# UARC_Sensor.net
KiCad netlist of a schematic drawn in Altium Designer
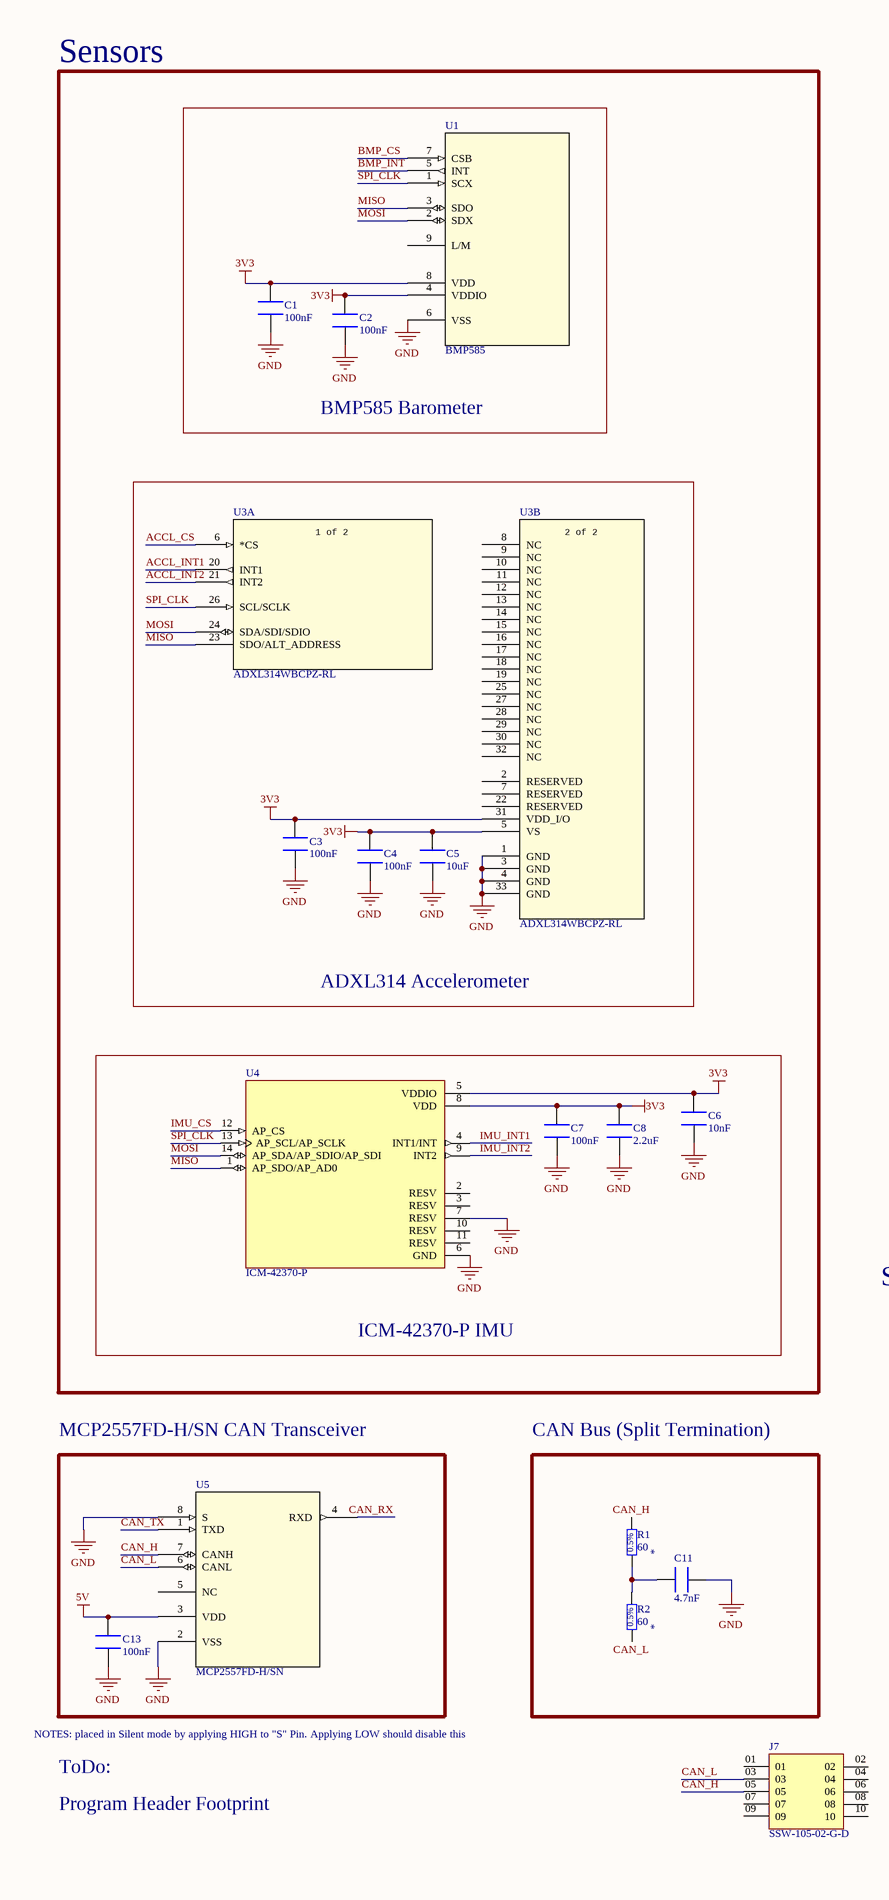
[diagram p0: UARC_Sensor.SchDoc, left]
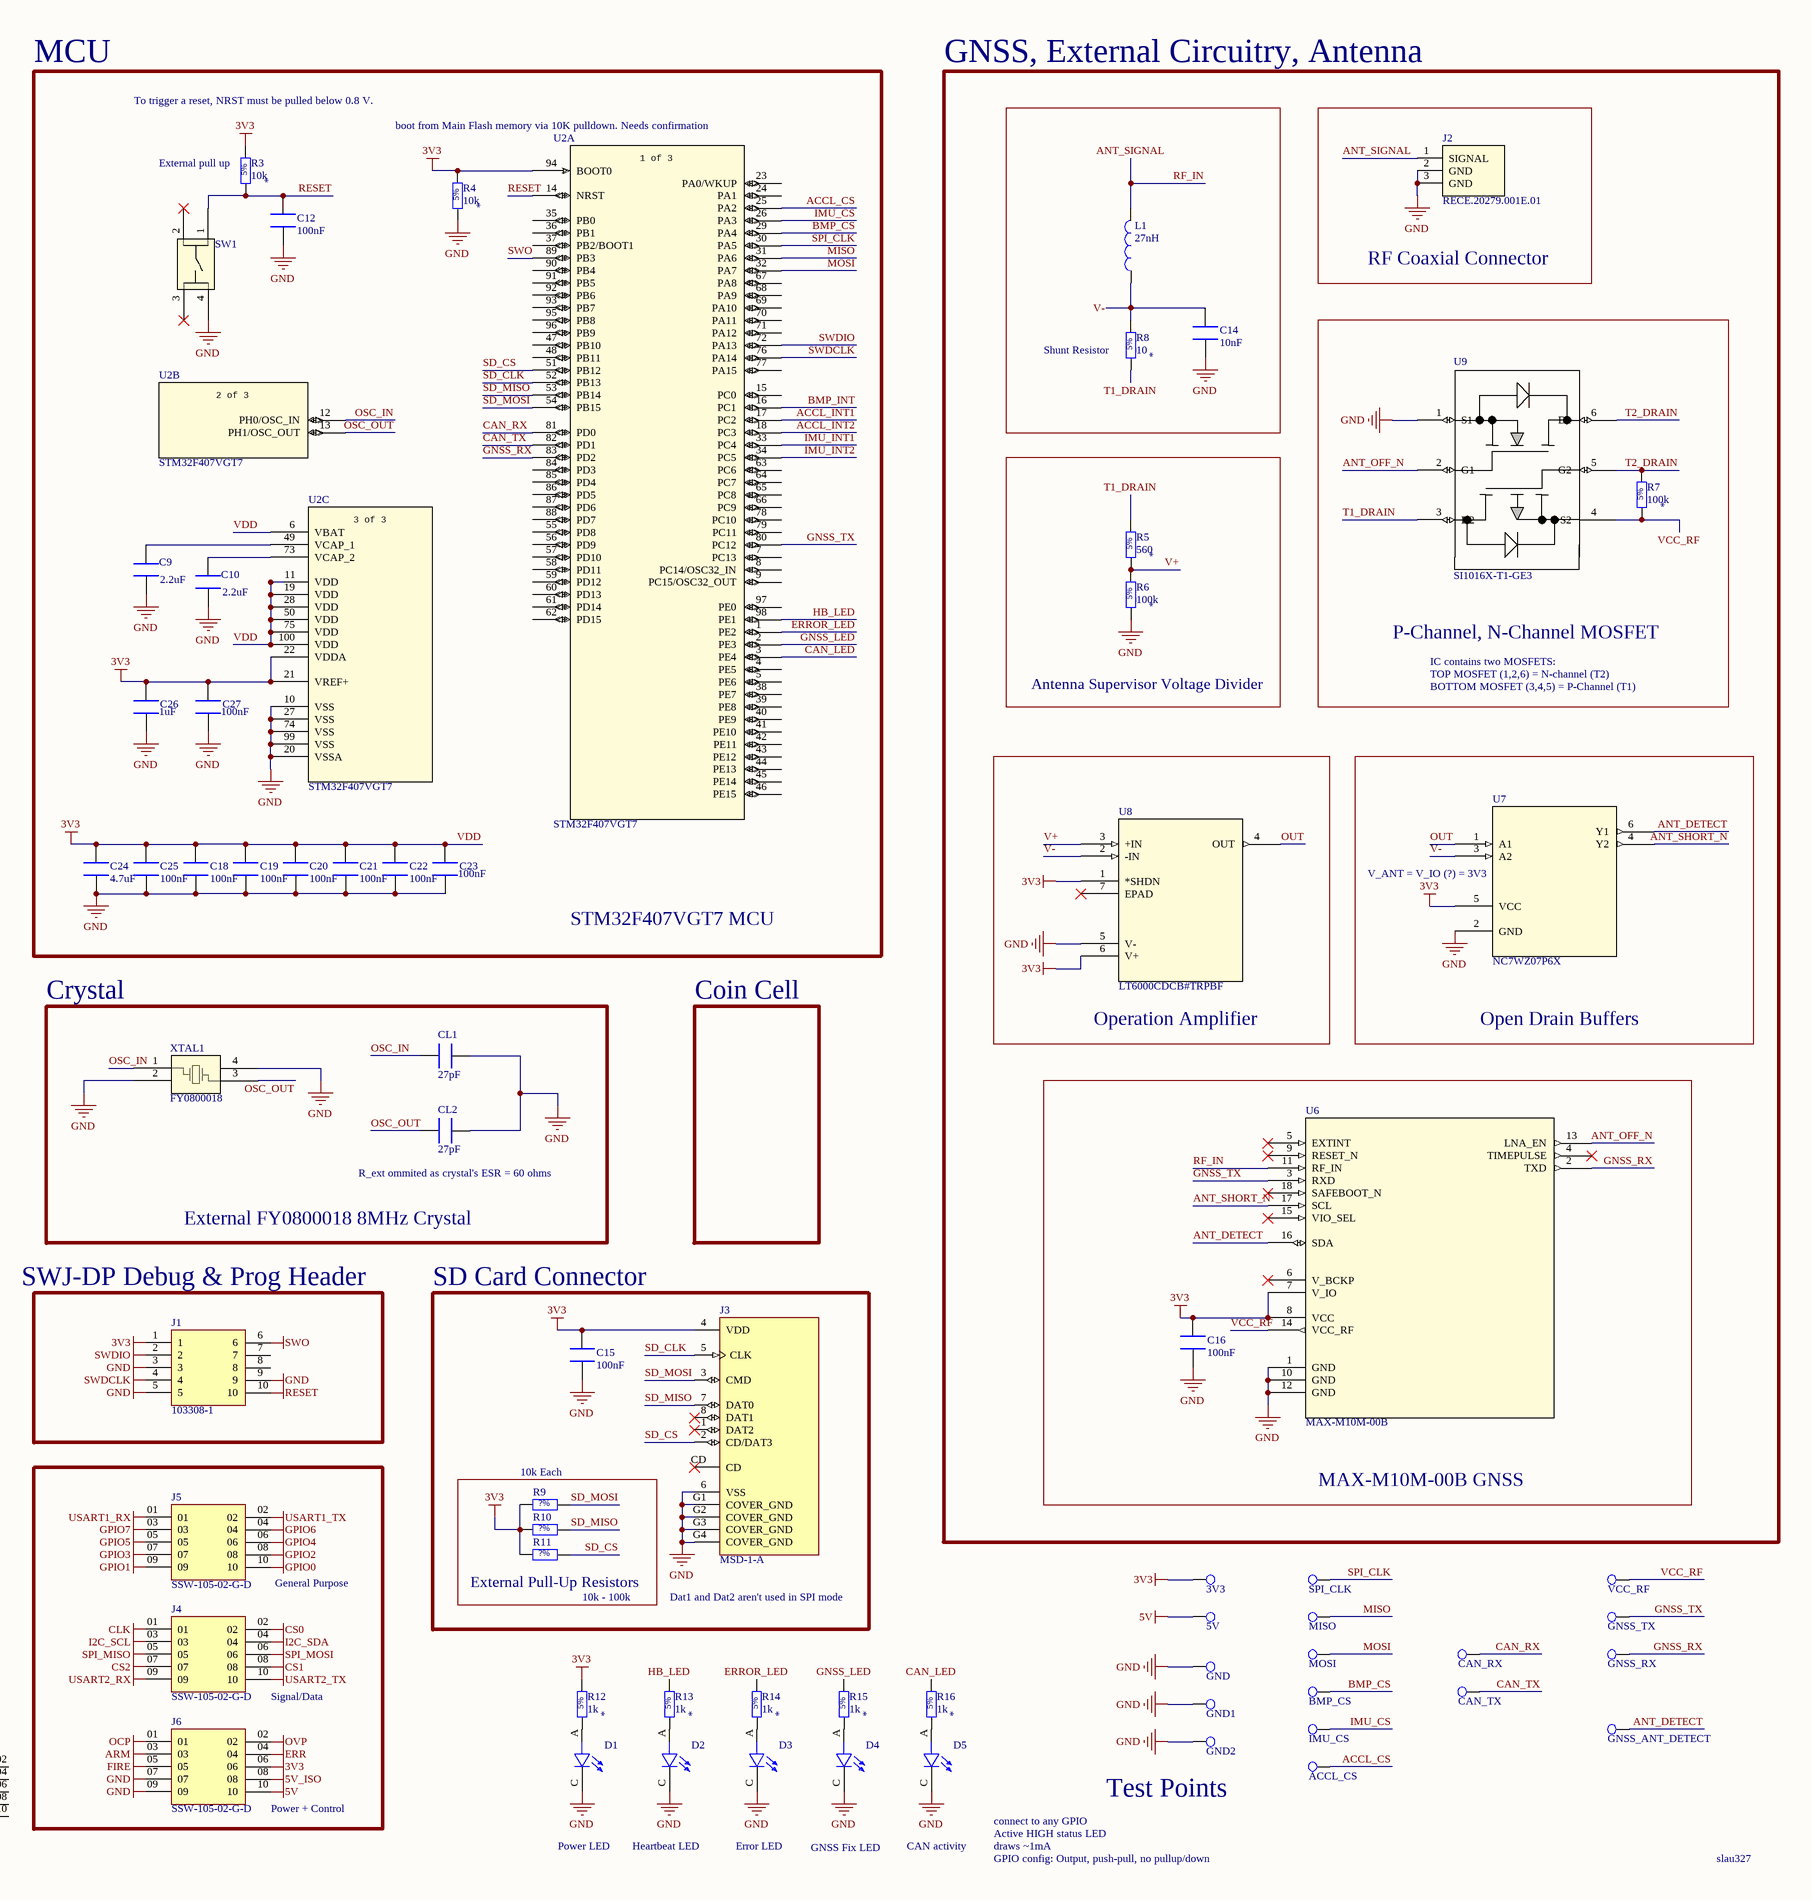
[diagram p1: UARC_Sensor.SchDoc, right]

(export (version "E")
  (design (tool "Eeschema 10.0.6"))
  (components
    (comp (ref "3V3")
      (value "Test Point")
      (footprint "APSS Generic Components:Test Point Pad Large")
      (libsource (lib "APSS Generic Components") (part "Test Point"))
    )
    (comp (ref "5V")
      (value "Test Point")
      (footprint "APSS Generic Components:Test Point Pad Large")
      (libsource (lib "APSS Generic Components") (part "Test Point"))
    )
    (comp (ref "ACCL_CS")
      (value "Test Point")
      (footprint "APSS Generic Components:Test Point Pad Large")
      (libsource (lib "APSS Generic Components") (part "Test Point"))
    )
    (comp (ref "BMP_CS")
      (value "Test Point")
      (footprint "APSS Generic Components:Test Point Pad Large")
      (libsource (lib "APSS Generic Components") (part "Test Point"))
    )
    (comp (ref "C1")
      (value "100nF")
      (footprint "APSS Flight Parts:CAPACITOR_0805_2012M-70N")
      (description "CUSTOM: 885012207016 0.1µF 0805 ±10% 10V X7R Ceramic Capacitor")
      (fields (field (name "TOLERANCE") "±20%") (field (name "MF PART NO.") "GRM21BR61E226ME44L"))
      (libsource (lib "") (part "GRM21BR61E226ME44L_1"))
    )
    (comp (ref "C2")
      (value "100nF")
      (footprint "APSS Flight Parts:CAPACITOR_0805_2012M-70N")
      (description "CUSTOM: 885012207016 0.1µF 0805 ±10% 10V X7R Ceramic Capacitor")
      (fields (field (name "TOLERANCE") "±20%") (field (name "MF PART NO.") "GRM21BR61E226ME44L"))
      (libsource (lib "APSS Flight Parts") (part "GRM21BR61E226ME44L"))
    )
    (comp (ref "C3")
      (value "100nF")
      (footprint "APSS Flight Parts:CAPACITOR_0805_2012M-70N")
      (description "CUSTOM: 885012207016 0.1µF 0805 ±10% 10V X7R Ceramic Capacitor")
      (fields (field (name "TOLERANCE") "±20%") (field (name "MF PART NO.") "GRM21BR61E226ME44L"))
      (libsource (lib "APSS Flight Parts") (part "GRM21BR61E226ME44L"))
    )
    (comp (ref "C4")
      (value "100nF")
      (footprint "APSS Flight Parts:CAPACITOR_0805_2012M-70N")
      (description "CUSTOM: 885012207016 0.1µF 0805 ±10% 10V X7R Ceramic Capacitor")
      (fields (field (name "TOLERANCE") "±20%") (field (name "MF PART NO.") "GRM21BR61E226ME44L"))
      (libsource (lib "APSS Flight Parts") (part "GRM21BR61E226ME44L"))
    )
    (comp (ref "C5")
      (value "10uF")
      (footprint "APSS Flight Parts:CAPACITOR_0805_2012M-70N")
      (description "CUSTOM: TACR106K010XTA 10µF 0805 ±10% 10V Tantalum Capacitor")
      (fields (field (name "TOLERANCE") "±20%") (field (name "MF PART NO.") "GRM21BR61E226ME44L"))
      (libsource (lib "APSS Flight Parts") (part "GRM21BR61E226ME44L"))
    )
    (comp (ref "C6")
      (value "10nF")
      (footprint "APSS Flight Parts:CAPACITOR_0805_2012M-70N")
      (description "CUSTOM: 885012207011, 10000pF 0805 ±10% 10 X7R  Ceramic Capacitor")
      (fields (field (name "TOLERANCE") "±20%") (field (name "MF PART NO.") "GRM21BR61E226ME44L"))
      (libsource (lib "APSS Flight Parts") (part "GRM21BR61E226ME44L"))
    )
    (comp (ref "C7")
      (value "100nF")
      (footprint "APSS Flight Parts:CAPACITOR_0805_2012M-70N")
      (description "CUSTOM: 885012207016 0.1µF 0805 ±10% 10V X7R Ceramic Capacitor")
      (fields (field (name "TOLERANCE") "±20%") (field (name "MF PART NO.") "GRM21BR61E226ME44L"))
      (libsource (lib "APSS Flight Parts") (part "GRM21BR61E226ME44L"))
    )
    (comp (ref "C8")
      (value "2.2uF")
      (footprint "APSS Flight Parts:CAPACITOR_0805_2012M-70N")
      (description "CUSTOM: GRM21BR71A225KA01L 2.2µF 0805 ±10% 10V X7R Ceramic Capacitor")
      (fields (field (name "TOLERANCE") "±20%") (field (name "MF PART NO.") "GRM21BR61E226ME44L"))
      (libsource (lib "APSS Flight Parts") (part "GRM21BR61E226ME44L"))
    )
    (comp (ref "C9")
      (value "2.2uF")
      (footprint "APSS Flight Parts:CAPACITOR_0805_2012M-70N")
      (description "CUSTOM: GRM21BR71A225KA01L 2.2µF 0805 ±10% 10V X7R Ceramic Capacitor")
      (fields (field (name "TOLERANCE") "±20%") (field (name "MF PART NO.") "GRM21BR61E226ME44L"))
      (libsource (lib "APSS Flight Parts") (part "GRM21BR61E226ME44L"))
    )
    (comp (ref "C10")
      (value "2.2uF")
      (footprint "APSS Flight Parts:CAPACITOR_0805_2012M-70N")
      (description "CUSTOM: GRM21BR71A225KA01L 2.2µF 0805 ±10% 10V X7R Ceramic Capacitor")
      (fields (field (name "TOLERANCE") "±20%") (field (name "MF PART NO.") "GRM21BR61E226ME44L"))
      (libsource (lib "APSS Flight Parts") (part "GRM21BR61E226ME44L"))
    )
    (comp (ref "C11")
      (value "4.7nF")
      (footprint "APSS Flight Parts:CAPACITOR_0805_2012M-70N")
      (description "CUSTOM: CC0805KRX7R9BB472 4700pF 0805 ±10% 50V X7R Ceramic Capacitor")
      (fields (field (name "TOLERANCE") "±20%") (field (name "MF PART NO.") "GRM21BR61E226ME44L"))
      (libsource (lib "APSS Flight Parts") (part "GRM21BR61E226ME44L"))
    )
    (comp (ref "C12")
      (value "100nF")
      (footprint "APSS Flight Parts:CAPACITOR_0805_2012M-70N")
      (description "CUSTOM: 885012207016 0.1µF 0805 ±10% 10V X7R Ceramic Capacitor")
      (fields (field (name "TOLERANCE") "±20%") (field (name "MF PART NO.") "GRM21BR61E226ME44L"))
      (libsource (lib "APSS Flight Parts") (part "GRM21BR61E226ME44L"))
    )
    (comp (ref "C13")
      (value "100nF")
      (footprint "APSS Flight Parts:CAPACITOR_0805_2012M-70N")
      (description "CUSTOM: 885012207016 0.1µF 0805 ±10% 10V X7R Ceramic Capacitor")
      (fields (field (name "TOLERANCE") "±20%") (field (name "MF PART NO.") "GRM21BR60J107ME15L"))
      (libsource (lib "APSS Flight Parts") (part "GRM21BR60J107ME15L"))
    )
    (comp (ref "C14")
      (value "10nF")
      (footprint "APSS Flight Parts:CAPACITOR_0402_1005M_55N")
      (description "CUSTOM: GRM155R71C103KA01D, 10000pF 0402 ±10% 16V X7R Ceramic Capacitor")
      (fields (field (name "TOLERANCE") "±10%") (field (name "MF PART NO.") "GRM155R61E225KE11J"))
      (libsource (lib "APSS Flight Parts") (part "GRM155R61E225KE11J"))
    )
    (comp (ref "C15")
      (value "100nF")
      (footprint "APSS Flight Parts:CAPACITOR_0805_2012M-70N")
      (description "CUSTOM: 885012207016 0.1µF 0805 ±10% 10V X7R Ceramic Capacitor")
      (fields (field (name "TOLERANCE") "±20%") (field (name "MF PART NO.") "GRM21BR61E226ME44L"))
      (libsource (lib "") (part "GRM21BR61E226ME44L_1"))
    )
    (comp (ref "C16")
      (value "100nF")
      (footprint "APSS Flight Parts:CAPACITOR_0805_2012M-70N")
      (description "CUSTOM: 885012207016 0.1µF 0805 ±10% 10V X7R Ceramic Capacitor")
      (fields (field (name "TOLERANCE") "±20%") (field (name "MF PART NO.") "GRM21BR61E226ME44L"))
      (libsource (lib "") (part "GRM21BR61E226ME44L_1"))
    )
    (comp (ref "C18")
      (value "100nF")
      (footprint "APSS Flight Parts:CAPACITOR_0805_2012M-70N")
      (description "CUSTOM: 885012207016 0.1µF 0805 ±10% 10V X7R Ceramic Capacitor")
      (fields (field (name "TOLERANCE") "±20%") (field (name "MF PART NO.") "GRM21BR61E226ME44L"))
      (libsource (lib "APSS Flight Parts") (part "GRM21BR61E226ME44L"))
    )
    (comp (ref "C19")
      (value "100nF")
      (footprint "APSS Flight Parts:CAPACITOR_0805_2012M-70N")
      (description "CUSTOM: 885012207016 0.1µF 0805 ±10% 10V X7R Ceramic Capacitor")
      (fields (field (name "TOLERANCE") "±20%") (field (name "MF PART NO.") "GRM21BR61E226ME44L"))
      (libsource (lib "APSS Flight Parts") (part "GRM21BR61E226ME44L"))
    )
    (comp (ref "C20")
      (value "100nF")
      (footprint "APSS Flight Parts:CAPACITOR_0805_2012M-70N")
      (description "CUSTOM: 885012207016 0.1µF 0805 ±10% 10V X7R Ceramic Capacitor")
      (fields (field (name "TOLERANCE") "±20%") (field (name "MF PART NO.") "GRM21BR61E226ME44L"))
      (libsource (lib "APSS Flight Parts") (part "GRM21BR61E226ME44L"))
    )
    (comp (ref "C21")
      (value "100nF")
      (footprint "APSS Flight Parts:CAPACITOR_0805_2012M-70N")
      (description "CUSTOM: 885012207016 0.1µF 0805 ±10% 10V X7R Ceramic Capacitor")
      (fields (field (name "TOLERANCE") "±20%") (field (name "MF PART NO.") "GRM21BR61E226ME44L"))
      (libsource (lib "APSS Flight Parts") (part "GRM21BR61E226ME44L"))
    )
    (comp (ref "C22")
      (value "100nF")
      (footprint "APSS Flight Parts:CAPACITOR_0805_2012M-70N")
      (description "CUSTOM: 885012207016 0.1µF 0805 ±10% 10V X7R Ceramic Capacitor")
      (fields (field (name "TOLERANCE") "±20%") (field (name "MF PART NO.") "GRM21BR61E226ME44L"))
      (libsource (lib "APSS Flight Parts") (part "GRM21BR61E226ME44L"))
    )
    (comp (ref "C23")
      (value "100nF")
      (footprint "APSS Flight Parts:CAPACITOR_0805_2012M-70N")
      (description "CUSTOM: 885012207016 0.1µF 0805 ±10% 10V X7R Ceramic Capacitor")
      (fields (field (name "TOLERANCE") "±20%") (field (name "MF PART NO.") "GRM21BR61E226ME44L"))
      (libsource (lib "APSS Flight Parts") (part "GRM21BR61E226ME44L"))
    )
    (comp (ref "C24")
      (value "4.7uF")
      (footprint "APSS Flight Parts:CAPACITOR_0603_1608M_100N")
      (description "CUSTOM:  GRM188Z71A475KE15D 4.7µF 0603 ±10% 10V X7R Ceramic Capacitor")
      (fields (field (name "TOLERANCE") "±10%") (field (name "MF PART NO.") "GRM188Z71A106KA73D"))
      (libsource (lib "APSS Flight Parts") (part "GRM188Z71A106KA73D"))
    )
    (comp (ref "C25")
      (value "100nF")
      (footprint "APSS Flight Parts:CAPACITOR_0805_2012M-70N")
      (description "CUSTOM: 885012207016 0.1µF 0805 ±10% 10V X7R Ceramic Capacitor")
      (fields (field (name "TOLERANCE") "±20%") (field (name "MF PART NO.") "GRM21BR61E226ME44L"))
      (libsource (lib "APSS Flight Parts") (part "GRM21BR61E226ME44L"))
    )
    (comp (ref "C26")
      (value "1uF")
      (footprint "APSS Flight Parts:CAPACITOR_0805_2012M-70N")
      (description "CUSTOM: 0805ZC105KAT2A 1µF 0805 ±10% 10V X7R  Ceramic Capacitor")
      (fields (field (name "TOLERANCE") "±20%") (field (name "MF PART NO.") "GRM21BR61E226ME44L"))
      (libsource (lib "APSS Flight Parts") (part "GRM21BR61E226ME44L"))
    )
    (comp (ref "C27")
      (value "100nF")
      (footprint "APSS Flight Parts:CAPACITOR_0805_2012M-70N")
      (description "CUSTOM: 885012207016 0.1µF 0805 ±10% 10V X7R Ceramic Capacitor")
      (fields (field (name "TOLERANCE") "±20%") (field (name "MF PART NO.") "GRM21BR61E226ME44L"))
      (libsource (lib "APSS Flight Parts") (part "GRM21BR61E226ME44L"))
    )
    (comp (ref "CAN_RX")
      (value "Test Point")
      (footprint "APSS Generic Components:Test Point Pad Large")
      (libsource (lib "APSS Generic Components") (part "Test Point"))
    )
    (comp (ref "CAN_TX")
      (value "Test Point")
      (footprint "APSS Generic Components:Test Point Pad Large")
      (libsource (lib "APSS Generic Components") (part "Test Point"))
    )
    (comp (ref "CL1")
      (value "27pF")
      (footprint "APSS Flight Parts:CAPACITOR_0805_2012M-70N")
      (description "CUSTOM: 600F270JT250XT4K 27pF 0805 ±5% 250V C0G, NP0 Ceramic Capacitor")
      (fields (field (name "TOLERANCE") "±20%") (field (name "MF PART NO.") "GRM21BR61E226ME44L"))
      (libsource (lib "APSS Flight Parts") (part "GRM21BR61E226ME44L"))
    )
    (comp (ref "CL2")
      (value "27pF")
      (footprint "APSS Flight Parts:CAPACITOR_0805_2012M-70N")
      (description "CUSTOM: 600F270JT250XT4K 27pF 0805 ±5% 250V C0G, NP0 Ceramic Capacitor")
      (fields (field (name "TOLERANCE") "±20%") (field (name "MF PART NO.") "GRM21BR61E226ME44L"))
      (libsource (lib "APSS Flight Parts") (part "GRM21BR61E226ME44L"))
    )
    (comp (ref "D1")
      (value "SML-D12U1WT86")
      (footprint "Custom_Footprints:LED_SML-D12U1WT86")
      (description "Red 620nm LED Indication - Discrete 2.2V 0603 (1608 Metric)")
      (fields (field (name "MF") "Rohm"))
      (libsource (lib "Custom_Library") (part "SML-D12U1WT86"))
    )
    (comp (ref "D2")
      (value "SML-D12U1WT86")
      (footprint "Custom_Footprints:LED_SML-D12U1WT86")
      (description "Red 620nm LED Indication - Discrete 2.2V 0603 (1608 Metric)")
      (fields (field (name "MF") "Rohm"))
      (libsource (lib "Custom_Library") (part "SML-D12U1WT86"))
    )
    (comp (ref "D3")
      (value "SML-D12U1WT86")
      (footprint "Custom_Footprints:LED_SML-D12U1WT86")
      (description "Red 620nm LED Indication - Discrete 2.2V 0603 (1608 Metric)")
      (fields (field (name "MF") "Rohm"))
      (libsource (lib "Custom_Library") (part "SML-D12U1WT86"))
    )
    (comp (ref "D4")
      (value "SML-D12U1WT86")
      (footprint "Custom_Footprints:LED_SML-D12U1WT86")
      (description "Red 620nm LED Indication - Discrete 2.2V 0603 (1608 Metric)")
      (fields (field (name "MF") "Rohm"))
      (libsource (lib "Custom_Library") (part "SML-D12U1WT86"))
    )
    (comp (ref "D5")
      (value "SML-D12U1WT86")
      (footprint "Custom_Footprints:LED_SML-D12U1WT86")
      (description "Red 620nm LED Indication - Discrete 2.2V 0603 (1608 Metric)")
      (fields (field (name "MF") "Rohm"))
      (libsource (lib "Custom_Library") (part "SML-D12U1WT86"))
    )
    (comp (ref "GND")
      (value "Test Point")
      (footprint "APSS Generic Components:Test Point Pad Large")
      (libsource (lib "APSS Generic Components") (part "Test Point"))
    )
    (comp (ref "GND1")
      (value "Test Point")
      (footprint "APSS Generic Components:Test Point Pad Large")
      (libsource (lib "APSS Generic Components") (part "Test Point"))
    )
    (comp (ref "GND2")
      (value "Test Point")
      (footprint "APSS Generic Components:Test Point Pad Large")
      (libsource (lib "APSS Generic Components") (part "Test Point"))
    )
    (comp (ref "GNSS_ANT_DETECT")
      (value "Test Point")
      (footprint "APSS Generic Components:Test Point Pad Large")
      (libsource (lib "APSS Generic Components") (part "Test Point"))
    )
    (comp (ref "GNSS_RX")
      (value "Test Point")
      (footprint "APSS Generic Components:Test Point Pad Large")
      (libsource (lib "APSS Generic Components") (part "Test Point"))
    )
    (comp (ref "GNSS_TX")
      (value "Test Point")
      (footprint "APSS Generic Components:Test Point Pad Large")
      (libsource (lib "APSS Generic Components") (part "Test Point"))
    )
    (comp (ref "IMU_CS")
      (value "Test Point")
      (footprint "APSS Generic Components:Test Point Pad Large")
      (libsource (lib "APSS Generic Components") (part "Test Point"))
    )
    (comp (ref "J1")
      (value "103308-1")
      (footprint "Custom_Footprints:TE_103308-1")
      (description "Header;  Pin;  Vertical;  Copper Alloy;  Thermoplastic;  10;  0.100 x 0.100 in.;  1 A")
      (fields (field (name "MF") "TE Connectivity"))
      (libsource (lib "Custom_Library") (part "103308-1"))
    )
    (comp (ref "J2")
      (value "RECE.20279.001E.01")
      (footprint "Custom_Footprints:CON3_RECE.20279.001E.01_TAL")
      (description "No Description Available")
      (fields (field (name "COPYRIGHT") "Copyright (C) 2025 Ultra Librarian. All rights reserved."))
      (libsource (lib "Custom_Library") (part "RECE.20279.001E.01"))
    )
    (comp (ref "J3")
      (value "MSD-1-A")
      (footprint "Custom_Footprints:CUI_MSD-1-A")
      (fields (field (name "MF") "Same Sky"))
      (libsource (lib "Custom_Library") (part "MSD-1-A"))
    )
    (comp (ref "J4")
      (value "SSW-105-02-G-D")
      (footprint "Custom_Footprints:SAMTEC_SSW-105-02-G-D")
      (fields (field (name "MF") "Samtec Inc."))
      (libsource (lib "Custom_Library") (part "SSW-105-02-G-D"))
    )
    (comp (ref "J5")
      (value "SSW-105-02-G-D")
      (footprint "Custom_Footprints:SAMTEC_SSW-105-02-G-D")
      (fields (field (name "MF") "Samtec Inc."))
      (libsource (lib "Custom_Library") (part "SSW-105-02-G-D"))
    )
    (comp (ref "J6")
      (value "SSW-105-02-G-D")
      (footprint "Custom_Footprints:SAMTEC_SSW-105-02-G-D")
      (fields (field (name "MF") "Samtec Inc."))
      (libsource (lib "Custom_Library") (part "SSW-105-02-G-D"))
    )
    (comp (ref "J7")
      (value "SSW-105-02-G-D")
      (footprint "Custom_Footprints:SAMTEC_SSW-105-02-G-D")
      (fields (field (name "MF") "Samtec Inc."))
      (libsource (lib "Custom_Library") (part "SSW-105-02-G-D"))
    )
    (comp (ref "L1")
      (value "27nH")
      (footprint "Custom_Footprints:INDC1005X55N")
      (description "LQG15HN2N2S02D 27nH 0402  Unshielded Multilayer Inductor 350 mA 460mOhm Max")
      (fields (field (name "MP") "LQG15HH27NJ02D"))
      (libsource (lib "Custom_Library") (part "LQG15HH27NJ02D"))
    )
    (comp (ref "MISO")
      (value "Test Point")
      (footprint "APSS Generic Components:Test Point Pad Large")
      (libsource (lib "APSS Generic Components") (part "Test Point"))
    )
    (comp (ref "MOSI")
      (value "Test Point")
      (footprint "APSS Generic Components:Test Point Pad Large")
      (libsource (lib "APSS Generic Components") (part "Test Point"))
    )
    (comp (ref "R1")
      (value "60")
      (footprint "APSS Flight Parts:RESISTOR_1206_3216M_55N")
      (description "CUSTOM: CRCW120660R0KNEAIF 60 Ohms 1206  ±10% 0.25W, 1/4W Chip Resistor,")
      (fields
        (field (name "TOLERANCE") "0.5%")
        (field (name "POWER") "0.52W")
        (field (name "MF PART NO.") "*")
      )
      (libsource (lib "APSS Flight Parts") (part "TNPW1206xxxxDE Series"))
    )
    (comp (ref "R2")
      (value "60")
      (footprint "APSS Flight Parts:RESISTOR_1206_3216M_55N")
      (description "CUSTOM: CRCW120660R0KNEAIF 60 Ohms 1206  ±10% 0.25W, 1/4W Chip Resistor,")
      (fields
        (field (name "TOLERANCE") "0.5%")
        (field (name "POWER") "0.52W")
        (field (name "MF PART NO.") "*")
      )
      (libsource (lib "APSS Flight Parts") (part "TNPW1206xxxxDE Series"))
    )
    (comp (ref "R3")
      (value "10k")
      (footprint "APSS Flight Parts:Resistor_0805_2012M-50N")
      (description "CUSTOM: CRCW080510K0FKEA 10 kOhms 0805  ±1% 0.25W, 1/4W Chip Resistor")
      (fields (field (name "TOLERANCE") "5%") (field (name "POWER") "1/8W") (field (name "MF PART NO.") "*"))
      (libsource (lib "APSS Flight Parts") (part "RMCF0805JT Series"))
    )
    (comp (ref "R4")
      (value "10k")
      (footprint "APSS Flight Parts:Resistor_0805_2012M-50N")
      (description "CUSTOM: CRCW080510K0FKEA 10 kOhms 0805  ±1% 0.25W, 1/4W Chip Resistor")
      (fields (field (name "TOLERANCE") "5%") (field (name "POWER") "1/8W") (field (name "MF PART NO.") "*"))
      (libsource (lib "APSS Flight Parts") (part "RMCF0805JT Series"))
    )
    (comp (ref "R5")
      (value "560")
      (footprint "APSS Flight Parts:RESISTOR_0402_1005M_37N")
      (description "CUSTOM: ERJ-2GEJ561X 560 Ohms 0402  ±5% 0.1W, 1/10W Chip Resistor")
      (fields (field (name "TOLERANCE") "5%") (field (name "POWER") "1/16W") (field (name "MF PART NO.") "*"))
      (libsource (lib "APSS Flight Parts") (part "RMCF0402JT Series"))
    )
    (comp (ref "R6")
      (value "100k")
      (footprint "APSS Flight Parts:RESISTOR_0402_1005M_37N")
      (description "CUSTOM: RK73B1ETTP104J 100 kOhms 0402 ±5% 0.1W, 1/10W Chip Resistor")
      (fields (field (name "TOLERANCE") "5%") (field (name "POWER") "1/16W") (field (name "MF PART NO.") "*"))
      (libsource (lib "APSS Flight Parts") (part "RMCF0402JT Series"))
    )
    (comp (ref "R7")
      (value "100k")
      (footprint "APSS Flight Parts:RESISTOR_0402_1005M_37N")
      (description "CUSTOM: RK73B1ETTP104J 100 kOhms 0402 ±5% 0.1W, 1/10W Chip Resistor")
      (fields (field (name "TOLERANCE") "5%") (field (name "POWER") "1/16W") (field (name "MF PART NO.") "*"))
      (libsource (lib "APSS Flight Parts") (part "RMCF0402JT Series"))
    )
    (comp (ref "R8")
      (value "10")
      (footprint "APSS Flight Parts:RESISTOR_0402_1005M_37N")
      (description "CUSTOM: SG73P1EWTTP100J 10 Ohms 0402 ±5% 0.25W, 1/4W Chip Resistor")
      (fields (field (name "TOLERANCE") "5%") (field (name "POWER") "1/16W") (field (name "MF PART NO.") "*"))
      (libsource (lib "APSS Flight Parts") (part "RMCF0402JT Series"))
    )
    (comp (ref "R9")
      (value "~")
      (footprint "RESISTOR_0805_2012M-50N")
      (description "CUSTOM: CRCW080510K0FKEA 10 kOhms 0805  ±1% 0.25W, 1/4W Chip Resistor")
      (fields (field (name "TOLERANCE") "?%"))
      (libsource (lib "APSS Generic Components") (part "Generic Resistor"))
    )
    (comp (ref "R10")
      (value "~")
      (footprint "RESISTOR_0805_2012M-50N")
      (description "CUSTOM: CRCW080510K0FKEA 10 kOhms 0805  ±1% 0.25W, 1/4W Chip Resistor")
      (fields (field (name "TOLERANCE") "?%"))
      (libsource (lib "APSS Generic Components") (part "Generic Resistor"))
    )
    (comp (ref "R11")
      (value "~")
      (footprint "RESISTOR_0805_2012M-50N")
      (description "CUSTOM: CRCW080510K0FKEA 10 kOhms 0805  ±1% 0.25W, 1/4W Chip Resistor")
      (fields (field (name "TOLERANCE") "?%"))
      (libsource (lib "APSS Generic Components") (part "Generic Resistor"))
    )
    (comp (ref "R12")
      (value "1k")
      (footprint "APSS Flight Parts:Resistor_0805_2012M-50N")
      (description "CUSTOM: CRCW08051K00FKEA 1 kOhms 0805 ±1% 0.25W, 1/4W Chip Resistor")
      (fields (field (name "TOLERANCE") "5%") (field (name "POWER") "1/8W") (field (name "MF PART NO.") "*"))
      (libsource (lib "APSS Flight Parts") (part "RMCF0805JT Series"))
    )
    (comp (ref "R13")
      (value "1k")
      (footprint "APSS Flight Parts:Resistor_0805_2012M-50N")
      (description "CUSTOM: CRCW08051K00FKEA 1 kOhms 0805 ±1% 0.25W, 1/4W Chip Resistor")
      (fields (field (name "TOLERANCE") "5%") (field (name "POWER") "1/8W") (field (name "MF PART NO.") "*"))
      (libsource (lib "APSS Flight Parts") (part "RMCF0805JT Series"))
    )
    (comp (ref "R14")
      (value "1k")
      (footprint "APSS Flight Parts:Resistor_0805_2012M-50N")
      (description "CUSTOM: CRCW08051K00FKEA 1 kOhms 0805 ±1% 0.25W, 1/4W Chip Resistor")
      (fields (field (name "TOLERANCE") "5%") (field (name "POWER") "1/8W") (field (name "MF PART NO.") "*"))
      (libsource (lib "APSS Flight Parts") (part "RMCF0805JT Series"))
    )
    (comp (ref "R15")
      (value "1k")
      (footprint "APSS Flight Parts:Resistor_0805_2012M-50N")
      (description "CUSTOM: CRCW08051K00FKEA 1 kOhms 0805 ±1% 0.25W, 1/4W Chip Resistor")
      (fields (field (name "TOLERANCE") "5%") (field (name "POWER") "1/8W") (field (name "MF PART NO.") "*"))
      (libsource (lib "APSS Flight Parts") (part "RMCF0805JT Series"))
    )
    (comp (ref "R16")
      (value "1k")
      (footprint "APSS Flight Parts:Resistor_0805_2012M-50N")
      (description "CUSTOM: CRCW08051K00FKEA 1 kOhms 0805 ±1% 0.25W, 1/4W Chip Resistor")
      (fields (field (name "TOLERANCE") "5%") (field (name "POWER") "1/8W") (field (name "MF PART NO.") "*"))
      (libsource (lib "APSS Flight Parts") (part "RMCF0805JT Series"))
    )
    (comp (ref "SPI_CLK")
      (value "Test Point")
      (footprint "APSS Generic Components:Test Point Pad Large")
      (libsource (lib "APSS Generic Components") (part "Test Point"))
    )
    (comp (ref "SW1")
      (value "PTS526 SM15 SMTR2 LFS")
      (footprint "Custom_Footprints:SON4_PTS526 SM15 SMTR2 LFS_CNK")
      (description "Description")
      (fields (field (name "COPYRIGHT") "Copyright (C) 2025 Ultra Librarian. All rights reserved."))
      (libsource (lib "Custom_Library") (part "PTS526 SM15 SMTR2 LFS"))
    )
    (comp (ref "U1")
      (value "BMP585")
      (footprint "Custom_Footprints:LGA9_BMP585_BOS")
      (description "No Description Available")
      (fields (field (name "COPYRIGHT") "Copyright (C) 2025 Ultra Librarian. All rights reserved."))
      (libsource (lib "Custom_Library") (part "BMP585"))
    )
    (comp (ref "U2")
      (value "STM32F407VGT7")
      (footprint "Custom_Footprints:LQFP100-14x14mm")
      (fields (field (name "COPYRIGHT") "Copyright (C) 2025 Ultra Librarian. All rights reserved."))
      (libsource (lib "Custom_Library") (part "STM32F407VGT7"))
    )
    (comp (ref "U3")
      (value "ADXL314WBCPZ-RL")
      (footprint "Custom_Footprints:LFCSP32_CP-32-17_ADI")
      (description "Â±200 g Range, 3-Axis Digital Accelerometer")
      (fields (field (name "COPYRIGHT") "Copyright (C) 2025 Ultra Librarian. All rights reserved."))
      (libsource (lib "Custom_Library") (part "ADXL314WBCPZ-RL"))
    )
    (comp (ref "U4")
      (value "ICM-42370-P")
      (footprint "Custom_Footprints:PQFN50P250X300X81-14N")
      (description "Accelerometer X, Y, Z Axis 2g, 4g, 8g, 16g 14-LGA (2.5x3)")
      (fields (field (name "MF") "InvenSense"))
      (libsource (lib "Custom_Library") (part "ICM-42370-P"))
    )
    (comp (ref "U5")
      (value "MCP2557FD-H/SN")
      (footprint "Custom_Footprints:SOIC8_SN_MCH")
      (description "No Description Available")
      (fields (field (name "COPYRIGHT") "Copyright (C) 2025 Ultra Librarian. All rights reserved."))
      (libsource (lib "Custom_Library") (part "MCP2557FD-HSN"))
    )
    (comp (ref "U6")
      (value "MAX-M10M-00B")
      (footprint "Custom_Footprints:MOD18_MAX-M10M_UBL")
      (description "No Description Available")
      (fields (field (name "COPYRIGHT") "Copyright (C) 2025 Ultra Librarian. All rights reserved."))
      (libsource (lib "Custom_Library") (part "MAX-M10M-00B"))
    )
    (comp (ref "U7")
      (value "NC7WZ07P6X")
      (footprint "Custom_Footprints:SC-88SC70-6SOT-363_419B-02_ONS")
      (description "Description")
      (fields (field (name "COPYRIGHT") "Copyright (C) 2025 Ultra Librarian. All rights reserved."))
      (libsource (lib "Custom_Library") (part "NC7WZ07P6X"))
    )
    (comp (ref "U8")
      (value "LT6000CDCB#TRPBF")
      (footprint "Custom_Footprints:DFN-6_DCB_LIT")
      (description "Single 1.8V, 13ÂµA Precision Rail-to-Rail Op Amp")
      (fields (field (name "COPYRIGHT") "Copyright (C) 2025 Ultra Librarian. All rights reserved."))
      (libsource (lib "Custom_Library") (part "LT6000CDCBTRPBF"))
    )
    (comp (ref "U9")
      (value "SI1016X-T1-GE3")
      (footprint "Custom_Footprints:SOT_X-T1-GE3_VIS")
      (description "COMPLEMENTARY N & P-CH 20-V (D-S) MOSFET")
      (fields (field (name "COPYRIGHT") "Copyright (C) 2025 Ultra Librarian. All rights reserved."))
      (libsource (lib "Custom_Library") (part "SI1016X-T1-GE3"))
    )
    (comp (ref "VCC_RF")
      (value "Test Point")
      (footprint "APSS Generic Components:Test Point Pad Large")
      (libsource (lib "APSS Generic Components") (part "Test Point"))
    )
    (comp (ref "XTAL1")
      (value "FY0800018")
      (footprint "Custom_Footprints:4xtal- 1-3xtal 2-4NC_DIO")
      (description "No Description Available")
      (fields (field (name "COPYRIGHT") "Copyright (C) 2025 Ultra Librarian. All rights reserved."))
      (libsource (lib "Custom_Library") (part "FY0800018"))
    )
  )
  (nets
    (net (code "1") (name "/ACCL_CS") (class "Default")
      (node (ref "ACCL_CS") (pin "1") (pinfunction "0_1") (pintype "passive"))
      (node (ref "U2") (pin "25") (pinfunction "PA2_25") (pintype "bidirectional"))
      (node (ref "U3") (pin "6") (pinfunction "*CS_6") (pintype "input"))
    )
    (net (code "2") (name "/ACCL_INT1") (class "Default")
      (node (ref "U2") (pin "17") (pinfunction "PC2_17") (pintype "bidirectional"))
      (node (ref "U3") (pin "20") (pinfunction "INT1_20") (pintype "output"))
    )
    (net (code "3") (name "/ACCL_INT2") (class "Default")
      (node (ref "U2") (pin "18") (pinfunction "PC3_18") (pintype "bidirectional"))
      (node (ref "U3") (pin "21") (pinfunction "INT2_21") (pintype "output"))
    )
    (net (code "4") (name "/ANT_DETECT") (class "Default")
      (node (ref "GNSS_ANT_DETECT") (pin "1") (pinfunction "0_1") (pintype "passive"))
      (node (ref "U6") (pin "16") (pinfunction "SDA_16") (pintype "bidirectional"))
      (node (ref "U7") (pin "6") (pinfunction "Y1_6") (pintype "output"))
    )
    (net (code "5") (name "/ANT_OFF_N") (class "Default")
      (node (ref "U6") (pin "13") (pinfunction "LNA_EN_13") (pintype "output"))
      (node (ref "U9") (pin "2") (pinfunction "G1_2") (pintype "bidirectional"))
    )
    (net (code "6") (name "/ANT_SHORT_N") (class "Default")
      (node (ref "U6") (pin "17") (pinfunction "SCL_17") (pintype "input"))
      (node (ref "U7") (pin "4") (pinfunction "Y2_4") (pintype "output"))
    )
    (net (code "7") (name "/ANT_SIGNAL") (class "Default")
      (node (ref "J2") (pin "1") (pinfunction "SIGNAL_1") (pintype "passive"))
      (node (ref "L1") (pin "2") (pinfunction "2_2") (pintype "passive"))
      (node (ref "U6") (pin "11") (pinfunction "RF_IN_11") (pintype "input"))
    )
    (net (code "8") (name "/BMP_CS") (class "Default")
      (node (ref "BMP_CS") (pin "1") (pinfunction "0_1") (pintype "passive"))
      (node (ref "U1") (pin "7") (pinfunction "CSB_7") (pintype "input"))
      (node (ref "U2") (pin "29") (pinfunction "PA4_29") (pintype "bidirectional"))
    )
    (net (code "9") (name "/BMP_INT") (class "Default")
      (node (ref "U1") (pin "5") (pinfunction "INT_5") (pintype "output"))
      (node (ref "U2") (pin "16") (pinfunction "PC1_16") (pintype "bidirectional"))
    )
    (net (code "10") (name "/CAN_H") (class "Default")
      (node (ref "J7") (pin "05") (pinfunction "05_05") (pintype "passive"))
      (node (ref "R1") (pin "2") (pinfunction "2_2") (pintype "passive"))
      (node (ref "U5") (pin "7") (pinfunction "CANH_7") (pintype "bidirectional"))
    )
    (net (code "11") (name "/CAN_L") (class "Default")
      (node (ref "J7") (pin "03") (pinfunction "03_03") (pintype "passive"))
      (node (ref "R2") (pin "1") (pinfunction "1_1") (pintype "passive"))
      (node (ref "U5") (pin "6") (pinfunction "CANL_6") (pintype "bidirectional"))
    )
    (net (code "12") (name "/CAN_LED") (class "Default")
      (node (ref "R16") (pin "2") (pinfunction "2_2") (pintype "passive"))
      (node (ref "U2") (pin "3") (pinfunction "PE4_3") (pintype "bidirectional"))
    )
    (net (code "13") (name "/CAN_RX") (class "Default")
      (node (ref "CAN_RX") (pin "1") (pinfunction "0_1") (pintype "passive"))
      (node (ref "U2") (pin "81") (pinfunction "PD0_81") (pintype "bidirectional"))
      (node (ref "U5") (pin "4") (pinfunction "RXD_4") (pintype "output"))
    )
    (net (code "14") (name "/CAN_TX") (class "Default")
      (node (ref "CAN_TX") (pin "1") (pinfunction "0_1") (pintype "passive"))
      (node (ref "U2") (pin "82") (pinfunction "PD1_82") (pintype "bidirectional"))
      (node (ref "U5") (pin "1") (pinfunction "TXD_1") (pintype "input"))
    )
    (net (code "15") (name "/ERROR_LED") (class "Default")
      (node (ref "R14") (pin "2") (pinfunction "2_2") (pintype "passive"))
      (node (ref "U2") (pin "1") (pinfunction "PE2_1") (pintype "bidirectional"))
    )
    (net (code "16") (name "/GNSS_LED") (class "Default")
      (node (ref "R15") (pin "2") (pinfunction "2_2") (pintype "passive"))
      (node (ref "U2") (pin "2") (pinfunction "PE3_2") (pintype "bidirectional"))
    )
    (net (code "17") (name "/GNSS_RX") (class "Default")
      (node (ref "GNSS_RX") (pin "1") (pinfunction "0_1") (pintype "passive"))
      (node (ref "U2") (pin "83") (pinfunction "PD2_83") (pintype "bidirectional"))
      (node (ref "U6") (pin "2") (pinfunction "TXD_2") (pintype "output"))
    )
    (net (code "18") (name "/GNSS_TX") (class "Default")
      (node (ref "GNSS_TX") (pin "1") (pinfunction "0_1") (pintype "passive"))
      (node (ref "U2") (pin "80") (pinfunction "PC12_80") (pintype "bidirectional"))
      (node (ref "U6") (pin "3") (pinfunction "RXD_3") (pintype "input"))
    )
    (net (code "19") (name "/HB_LED") (class "Default")
      (node (ref "R13") (pin "2") (pinfunction "2_2") (pintype "passive"))
      (node (ref "U2") (pin "98") (pinfunction "PE1_98") (pintype "bidirectional"))
    )
    (net (code "20") (name "/IMU_CS") (class "Default")
      (node (ref "IMU_CS") (pin "1") (pinfunction "0_1") (pintype "passive"))
      (node (ref "U2") (pin "26") (pinfunction "PA3_26") (pintype "bidirectional"))
      (node (ref "U4") (pin "12") (pinfunction "AP_CS_12") (pintype "input"))
    )
    (net (code "21") (name "/IMU_INT1") (class "Default")
      (node (ref "U2") (pin "33") (pinfunction "PC4_33") (pintype "bidirectional"))
      (node (ref "U4") (pin "4") (pinfunction "INT1/INT_4") (pintype "output"))
    )
    (net (code "22") (name "/IMU_INT2") (class "Default")
      (node (ref "U2") (pin "34") (pinfunction "PC5_34") (pintype "bidirectional"))
      (node (ref "U4") (pin "9") (pinfunction "INT2_9") (pintype "output"))
    )
    (net (code "23") (name "/MISO") (class "Default")
      (node (ref "MISO") (pin "1") (pinfunction "0_1") (pintype "passive"))
      (node (ref "U1") (pin "3") (pinfunction "SDO_3") (pintype "bidirectional"))
      (node (ref "U2") (pin "31") (pinfunction "PA6_31") (pintype "bidirectional"))
      (node (ref "U3") (pin "23") (pinfunction "SDO/ALT_ADDRESS_23") (pintype "passive"))
      (node (ref "U4") (pin "1") (pinfunction "AP_SDO/AP_AD0_1") (pintype "bidirectional"))
    )
    (net (code "24") (name "/MOSI") (class "Default")
      (node (ref "MOSI") (pin "1") (pinfunction "0_1") (pintype "passive"))
      (node (ref "U1") (pin "2") (pinfunction "SDX_2") (pintype "bidirectional"))
      (node (ref "U2") (pin "32") (pinfunction "PA7_32") (pintype "bidirectional"))
      (node (ref "U3") (pin "24") (pinfunction "SDA/SDI/SDIO_24") (pintype "bidirectional"))
      (node (ref "U4") (pin "14") (pinfunction "AP_SDA/AP_SDIO/AP_SDI_14") (pintype "bidirectional"))
    )
    (net (code "25") (name "/OSC_IN") (class "Default")
      (node (ref "CL1") (pin "1") (pinfunction "1_1") (pintype "passive"))
      (node (ref "U2") (pin "12") (pinfunction "PH0/OSC_IN_12") (pintype "bidirectional"))
      (node (ref "XTAL1") (pin "1") (pinfunction "1_1") (pintype "passive"))
    )
    (net (code "26") (name "/OSC_OUT") (class "Default")
      (node (ref "CL2") (pin "1") (pinfunction "1_1") (pintype "passive"))
      (node (ref "U2") (pin "13") (pinfunction "PH1/OSC_OUT_13") (pintype "bidirectional"))
      (node (ref "XTAL1") (pin "3") (pinfunction "3_3") (pintype "passive"))
    )
    (net (code "27") (name "/OUT") (class "Default")
      (node (ref "U7") (pin "1") (pinfunction "A1_1") (pintype "input"))
      (node (ref "U8") (pin "4") (pinfunction "OUT_4") (pintype "output"))
    )
    (net (code "28") (name "/SD_CLK") (class "Default")
      (node (ref "J3") (pin "5") (pinfunction "CLK_5") (pintype "input"))
      (node (ref "U2") (pin "52") (pinfunction "PB13_52") (pintype "bidirectional"))
    )
    (net (code "29") (name "/SD_CS") (class "Default")
      (node (ref "J3") (pin "2") (pinfunction "CD/DAT3_2") (pintype "bidirectional"))
      (node (ref "R11") (pin "2") (pinfunction "2_2") (pintype "passive"))
      (node (ref "U2") (pin "51") (pinfunction "PB12_51") (pintype "bidirectional"))
    )
    (net (code "30") (name "/SD_MISO") (class "Default")
      (node (ref "J3") (pin "7") (pinfunction "DAT0_7") (pintype "bidirectional"))
      (node (ref "R10") (pin "2") (pinfunction "2_2") (pintype "passive"))
      (node (ref "U2") (pin "53") (pinfunction "PB14_53") (pintype "bidirectional"))
    )
    (net (code "31") (name "/SD_MOSI") (class "Default")
      (node (ref "J3") (pin "3") (pinfunction "CMD_3") (pintype "bidirectional"))
      (node (ref "R9") (pin "2") (pinfunction "2_2") (pintype "passive"))
      (node (ref "U2") (pin "54") (pinfunction "PB15_54") (pintype "bidirectional"))
    )
    (net (code "32") (name "/SPI_CLK") (class "Default")
      (node (ref "SPI_CLK") (pin "1") (pinfunction "0_1") (pintype "passive"))
      (node (ref "U1") (pin "1") (pinfunction "SCX_1") (pintype "input"))
      (node (ref "U2") (pin "30") (pinfunction "PA5_30") (pintype "bidirectional"))
      (node (ref "U3") (pin "26") (pinfunction "SCL/SCLK_26") (pintype "input"))
      (node (ref "U4") (pin "13") (pinfunction "AP_SCL/AP_SCLK_13") (pintype "input"))
    )
    (net (code "33") (name "/T1_DRAIN") (class "Default")
      (node (ref "R5") (pin "2") (pinfunction "2_2") (pintype "passive"))
      (node (ref "R8") (pin "1") (pinfunction "1_1") (pintype "passive"))
      (node (ref "U9") (pin "3") (pinfunction "D2_3") (pintype "bidirectional"))
    )
    (net (code "34") (name "/T2_DRAIN") (class "Default")
      (node (ref "R7") (pin "2") (pinfunction "2_2") (pintype "passive"))
      (node (ref "U9") (pin "5") (pinfunction "G2_5") (pintype "bidirectional"))
      (node (ref "U9") (pin "6") (pinfunction "D1_6") (pintype "bidirectional"))
    )
    (net (code "35") (name "/V+") (class "Default")
      (node (ref "R5") (pin "1") (pinfunction "1_1") (pintype "passive"))
      (node (ref "R6") (pin "2") (pinfunction "2_2") (pintype "passive"))
      (node (ref "U8") (pin "3") (pinfunction "+IN_3") (pintype "input"))
    )
    (net (code "36") (name "/V-") (class "Default")
      (node (ref "C14") (pin "2") (pinfunction "2_2") (pintype "passive"))
      (node (ref "L1") (pin "1") (pinfunction "1_1") (pintype "passive"))
      (node (ref "R8") (pin "2") (pinfunction "2_2") (pintype "passive"))
      (node (ref "U7") (pin "3") (pinfunction "A2_3") (pintype "input"))
      (node (ref "U8") (pin "2") (pinfunction "-IN_2") (pintype "input"))
    )
    (net (code "37") (name "/VCC_RF") (class "Default")
      (node (ref "R7") (pin "1") (pinfunction "1_1") (pintype "passive"))
      (node (ref "U6") (pin "14") (pinfunction "VCC_RF_14") (pintype "output"))
      (node (ref "U9") (pin "4") (pinfunction "S2_4") (pintype "passive"))
      (node (ref "VCC_RF") (pin "1") (pinfunction "0_1") (pintype "passive"))
    )
    (net (code "38") (name "3V3") (class "Default")
      (node (ref "3V3") (pin "1") (pinfunction "0_1") (pintype "passive"))
      (node (ref "C1") (pin "2") (pinfunction "2_2") (pintype "passive"))
      (node (ref "C15") (pin "2") (pinfunction "2_2") (pintype "passive"))
      (node (ref "C16") (pin "2") (pinfunction "2_2") (pintype "passive"))
      (node (ref "C18") (pin "1") (pinfunction "1_1") (pintype "passive"))
      (node (ref "C19") (pin "1") (pinfunction "1_1") (pintype "passive"))
      (node (ref "C2") (pin "1") (pinfunction "1_1") (pintype "passive"))
      (node (ref "C20") (pin "1") (pinfunction "1_1") (pintype "passive"))
      (node (ref "C21") (pin "1") (pinfunction "1_1") (pintype "passive"))
      (node (ref "C22") (pin "1") (pinfunction "1_1") (pintype "passive"))
      (node (ref "C23") (pin "1") (pinfunction "1_1") (pintype "passive"))
      (node (ref "C24") (pin "2") (pinfunction "2_2") (pintype "passive"))
      (node (ref "C25") (pin "1") (pinfunction "1_1") (pintype "passive"))
      (node (ref "C26") (pin "1") (pinfunction "1_1") (pintype "passive"))
      (node (ref "C27") (pin "1") (pinfunction "1_1") (pintype "passive"))
      (node (ref "C3") (pin "1") (pinfunction "1_1") (pintype "passive"))
      (node (ref "C4") (pin "1") (pinfunction "1_1") (pintype "passive"))
      (node (ref "C5") (pin "1") (pinfunction "1_1") (pintype "passive"))
      (node (ref "C6") (pin "1") (pinfunction "1_1") (pintype "passive"))
      (node (ref "C7") (pin "1") (pinfunction "1_1") (pintype "passive"))
      (node (ref "C8") (pin "1") (pinfunction "1_1") (pintype "passive"))
      (node (ref "J1") (pin "1") (pinfunction "1_1") (pintype "passive"))
      (node (ref "J3") (pin "4") (pinfunction "VDD_4") (pintype "power_in"))
      (node (ref "J6") (pin "06") (pinfunction "06_06") (pintype "passive"))
      (node (ref "R10") (pin "1") (pinfunction "1_1") (pintype "passive"))
      (node (ref "R11") (pin "1") (pinfunction "1_1") (pintype "passive"))
      (node (ref "R12") (pin "2") (pinfunction "2_2") (pintype "passive"))
      (node (ref "R3") (pin "2") (pinfunction "2_2") (pintype "passive"))
      (node (ref "R4") (pin "2") (pinfunction "2_2") (pintype "passive"))
      (node (ref "R9") (pin "1") (pinfunction "1_1") (pintype "passive"))
      (node (ref "U1") (pin "4") (pinfunction "VDDIO_4") (pintype "power_in"))
      (node (ref "U1") (pin "8") (pinfunction "VDD_8") (pintype "power_in"))
      (node (ref "U2") (pin "100") (pinfunction "VDD_100") (pintype "power_in"))
      (node (ref "U2") (pin "11") (pinfunction "VDD_11") (pintype "power_in"))
      (node (ref "U2") (pin "19") (pinfunction "VDD_19") (pintype "power_in"))
      (node (ref "U2") (pin "21") (pinfunction "VREF+_21") (pintype "power_in"))
      (node (ref "U2") (pin "22") (pinfunction "VDDA_22") (pintype "power_in"))
      (node (ref "U2") (pin "28") (pinfunction "VDD_28") (pintype "power_in"))
      (node (ref "U2") (pin "50") (pinfunction "VDD_50") (pintype "power_in"))
      (node (ref "U2") (pin "6") (pinfunction "VBAT_6") (pintype "power_in"))
      (node (ref "U2") (pin "75") (pinfunction "VDD_75") (pintype "power_in"))
      (node (ref "U2") (pin "94") (pinfunction "BOOT0_94") (pintype "input"))
      (node (ref "U3") (pin "31") (pinfunction "VDD_I/O_31") (pintype "power_in"))
      (node (ref "U3") (pin "5") (pinfunction "VS_5") (pintype "power_in"))
      (node (ref "U4") (pin "5") (pinfunction "VDDIO_5") (pintype "power_in"))
      (node (ref "U4") (pin "8") (pinfunction "VDD_8") (pintype "power_in"))
      (node (ref "U6") (pin "7") (pinfunction "V_IO_7") (pintype "power_in"))
      (node (ref "U6") (pin "8") (pinfunction "VCC_8") (pintype "power_in"))
      (node (ref "U7") (pin "5") (pinfunction "VCC_5") (pintype "power_in"))
      (node (ref "U8") (pin "1") (pinfunction "*SHDN_1") (pintype "passive"))
      (node (ref "U8") (pin "6") (pinfunction "V+_6") (pintype "power_in"))
    )
    (net (code "39") (name "5V") (class "Default")
      (node (ref "5V") (pin "1") (pinfunction "0_1") (pintype "passive"))
      (node (ref "C13") (pin "2") (pinfunction "2_2") (pintype "passive"))
      (node (ref "J6") (pin "10") (pinfunction "10_10") (pintype "passive"))
      (node (ref "U5") (pin "3") (pinfunction "VDD_3") (pintype "power_in"))
    )
    (net (code "40") (name "5V_ISO") (class "Default")
      (node (ref "J6") (pin "08") (pinfunction "08_08") (pintype "passive"))
    )
    (net (code "41") (name "ARM") (class "Default")
      (node (ref "J6") (pin "03") (pinfunction "03_03") (pintype "passive"))
    )
    (net (code "42") (name "CLK") (class "Default")
      (node (ref "J4") (pin "01") (pinfunction "01_01") (pintype "passive"))
    )
    (net (code "43") (name "CS0") (class "Default")
      (node (ref "J4") (pin "02") (pinfunction "02_02") (pintype "passive"))
    )
    (net (code "44") (name "CS1") (class "Default")
      (node (ref "J4") (pin "08") (pinfunction "08_08") (pintype "passive"))
    )
    (net (code "45") (name "CS2") (class "Default")
      (node (ref "J4") (pin "07") (pinfunction "07_07") (pintype "passive"))
    )
    (net (code "46") (name "ERR") (class "Default")
      (node (ref "J6") (pin "04") (pinfunction "04_04") (pintype "passive"))
    )
    (net (code "47") (name "FIRE") (class "Default")
      (node (ref "J6") (pin "05") (pinfunction "05_05") (pintype "passive"))
    )
    (net (code "48") (name "GND") (class "Default")
      (node (ref "C1") (pin "1") (pinfunction "1_1") (pintype "passive"))
      (node (ref "C10") (pin "2") (pinfunction "2_2") (pintype "passive"))
      (node (ref "C11") (pin "2") (pinfunction "2_2") (pintype "passive"))
      (node (ref "C12") (pin "2") (pinfunction "2_2") (pintype "passive"))
      (node (ref "C13") (pin "1") (pinfunction "1_1") (pintype "passive"))
      (node (ref "C14") (pin "1") (pinfunction "1_1") (pintype "passive"))
      (node (ref "C15") (pin "1") (pinfunction "1_1") (pintype "passive"))
      (node (ref "C16") (pin "1") (pinfunction "1_1") (pintype "passive"))
      (node (ref "C18") (pin "2") (pinfunction "2_2") (pintype "passive"))
      (node (ref "C19") (pin "2") (pinfunction "2_2") (pintype "passive"))
      (node (ref "C2") (pin "2") (pinfunction "2_2") (pintype "passive"))
      (node (ref "C20") (pin "2") (pinfunction "2_2") (pintype "passive"))
      (node (ref "C21") (pin "2") (pinfunction "2_2") (pintype "passive"))
      (node (ref "C22") (pin "2") (pinfunction "2_2") (pintype "passive"))
      (node (ref "C23") (pin "2") (pinfunction "2_2") (pintype "passive"))
      (node (ref "C24") (pin "1") (pinfunction "1_1") (pintype "passive"))
      (node (ref "C25") (pin "2") (pinfunction "2_2") (pintype "passive"))
      (node (ref "C26") (pin "2") (pinfunction "2_2") (pintype "passive"))
      (node (ref "C27") (pin "2") (pinfunction "2_2") (pintype "passive"))
      (node (ref "C3") (pin "2") (pinfunction "2_2") (pintype "passive"))
      (node (ref "C4") (pin "2") (pinfunction "2_2") (pintype "passive"))
      (node (ref "C5") (pin "2") (pinfunction "2_2") (pintype "passive"))
      (node (ref "C6") (pin "2") (pinfunction "2_2") (pintype "passive"))
      (node (ref "C7") (pin "2") (pinfunction "2_2") (pintype "passive"))
      (node (ref "C8") (pin "2") (pinfunction "2_2") (pintype "passive"))
      (node (ref "C9") (pin "2") (pinfunction "2_2") (pintype "passive"))
      (node (ref "CL1") (pin "2") (pinfunction "2_2") (pintype "passive"))
      (node (ref "CL2") (pin "2") (pinfunction "2_2") (pintype "passive"))
      (node (ref "D1") (pin "C") (pinfunction "C_C") (pintype "passive"))
      (node (ref "D2") (pin "C") (pinfunction "C_C") (pintype "passive"))
      (node (ref "D3") (pin "C") (pinfunction "C_C") (pintype "passive"))
      (node (ref "D4") (pin "C") (pinfunction "C_C") (pintype "passive"))
      (node (ref "D5") (pin "C") (pinfunction "C_C") (pintype "passive"))
      (node (ref "GND") (pin "1") (pinfunction "0_1") (pintype "passive"))
      (node (ref "GND1") (pin "1") (pinfunction "0_1") (pintype "passive"))
      (node (ref "GND2") (pin "1") (pinfunction "0_1") (pintype "passive"))
      (node (ref "J1") (pin "3") (pinfunction "3_3") (pintype "passive"))
      (node (ref "J1") (pin "5") (pinfunction "5_5") (pintype "passive"))
      (node (ref "J1") (pin "9") (pinfunction "9_9") (pintype "passive"))
      (node (ref "J2") (pin "2") (pinfunction "GND_2") (pintype "passive"))
      (node (ref "J2") (pin "3") (pinfunction "GND_3") (pintype "passive"))
      (node (ref "J3") (pin "6") (pinfunction "VSS_6") (pintype "power_in"))
      (node (ref "J3") (pin "G1") (pinfunction "COVER_GND_G1") (pintype "power_in"))
      (node (ref "J3") (pin "G2") (pinfunction "COVER_GND_G2") (pintype "power_in"))
      (node (ref "J3") (pin "G3") (pinfunction "COVER_GND_G3") (pintype "power_in"))
      (node (ref "J3") (pin "G4") (pinfunction "COVER_GND_G4") (pintype "power_in"))
      (node (ref "J6") (pin "07") (pinfunction "07_07") (pintype "passive"))
      (node (ref "J6") (pin "09") (pinfunction "09_09") (pintype "passive"))
      (node (ref "R4") (pin "1") (pinfunction "1_1") (pintype "passive"))
      (node (ref "R6") (pin "1") (pinfunction "1_1") (pintype "passive"))
      (node (ref "SW1") (pin "4") (pinfunction "4_4") (pintype "passive"))
      (node (ref "U1") (pin "6") (pinfunction "VSS_6") (pintype "power_in"))
      (node (ref "U2") (pin "10") (pinfunction "VSS_10") (pintype "power_in"))
      (node (ref "U2") (pin "20") (pinfunction "VSSA_20") (pintype "power_in"))
      (node (ref "U2") (pin "27") (pinfunction "VSS_27") (pintype "power_in"))
      (node (ref "U2") (pin "74") (pinfunction "VSS_74") (pintype "power_in"))
      (node (ref "U2") (pin "99") (pinfunction "VSS_99") (pintype "power_in"))
      (node (ref "U3") (pin "1") (pinfunction "GND_1") (pintype "power_in"))
      (node (ref "U3") (pin "3") (pinfunction "GND_3") (pintype "power_in"))
      (node (ref "U3") (pin "33") (pinfunction "GND_33") (pintype "power_in"))
      (node (ref "U3") (pin "4") (pinfunction "GND_4") (pintype "power_in"))
      (node (ref "U4") (pin "6") (pinfunction "GND_6") (pintype "power_in"))
      (node (ref "U4") (pin "7") (pinfunction "RESV_7") (pintype "passive"))
      (node (ref "U5") (pin "2") (pinfunction "VSS_2") (pintype "power_in"))
      (node (ref "U5") (pin "8") (pinfunction "S_8") (pintype "input"))
      (node (ref "U6") (pin "1") (pinfunction "GND_1") (pintype "power_in"))
      (node (ref "U6") (pin "10") (pinfunction "GND_10") (pintype "power_in"))
      (node (ref "U6") (pin "12") (pinfunction "GND_12") (pintype "power_in"))
      (node (ref "U7") (pin "2") (pinfunction "GND_2") (pintype "power_in"))
      (node (ref "U8") (pin "5") (pinfunction "V-_5") (pintype "power_in"))
      (node (ref "U9") (pin "1") (pinfunction "S1_1") (pintype "bidirectional"))
      (node (ref "XTAL1") (pin "2") (pinfunction "2_2") (pintype "passive"))
      (node (ref "XTAL1") (pin "4") (pinfunction "4_4") (pintype "passive"))
    )
    (net (code "49") (name "GPIO0") (class "Default")
      (node (ref "J5") (pin "10") (pinfunction "10_10") (pintype "passive"))
    )
    (net (code "50") (name "GPIO1") (class "Default")
      (node (ref "J5") (pin "09") (pinfunction "09_09") (pintype "passive"))
    )
    (net (code "51") (name "GPIO2") (class "Default")
      (node (ref "J5") (pin "08") (pinfunction "08_08") (pintype "passive"))
    )
    (net (code "52") (name "GPIO3") (class "Default")
      (node (ref "J5") (pin "07") (pinfunction "07_07") (pintype "passive"))
    )
    (net (code "53") (name "GPIO4") (class "Default")
      (node (ref "J5") (pin "06") (pinfunction "06_06") (pintype "passive"))
    )
    (net (code "54") (name "GPIO5") (class "Default")
      (node (ref "J5") (pin "05") (pinfunction "05_05") (pintype "passive"))
    )
    (net (code "55") (name "GPIO6") (class "Default")
      (node (ref "J5") (pin "04") (pinfunction "04_04") (pintype "passive"))
    )
    (net (code "56") (name "GPIO7") (class "Default")
      (node (ref "J5") (pin "03") (pinfunction "03_03") (pintype "passive"))
    )
    (net (code "57") (name "I2C_SCL") (class "Default")
      (node (ref "J4") (pin "03") (pinfunction "03_03") (pintype "passive"))
    )
    (net (code "58") (name "I2C_SDA") (class "Default")
      (node (ref "J4") (pin "04") (pinfunction "04_04") (pintype "passive"))
    )
    (net (code "59") (name "Net-(C11-Pad1)") (class "Default")
      (node (ref "C11") (pin "1") (pinfunction "1_1") (pintype "passive"))
      (node (ref "R1") (pin "1") (pinfunction "1_1") (pintype "passive"))
      (node (ref "R2") (pin "2") (pinfunction "2_2") (pintype "passive"))
    )
    (net (code "60") (name "Net-(D1-PadA)") (class "Default")
      (node (ref "D1") (pin "A") (pinfunction "A_A") (pintype "passive"))
      (node (ref "R12") (pin "1") (pinfunction "1_1") (pintype "passive"))
    )
    (net (code "61") (name "Net-(D2-PadA)") (class "Default")
      (node (ref "D2") (pin "A") (pinfunction "A_A") (pintype "passive"))
      (node (ref "R13") (pin "1") (pinfunction "1_1") (pintype "passive"))
    )
    (net (code "62") (name "Net-(D3-PadA)") (class "Default")
      (node (ref "D3") (pin "A") (pinfunction "A_A") (pintype "passive"))
      (node (ref "R14") (pin "1") (pinfunction "1_1") (pintype "passive"))
    )
    (net (code "63") (name "Net-(D4-PadA)") (class "Default")
      (node (ref "D4") (pin "A") (pinfunction "A_A") (pintype "passive"))
      (node (ref "R15") (pin "1") (pinfunction "1_1") (pintype "passive"))
    )
    (net (code "64") (name "Net-(D5-PadA)") (class "Default")
      (node (ref "D5") (pin "A") (pinfunction "A_A") (pintype "passive"))
      (node (ref "R16") (pin "1") (pinfunction "1_1") (pintype "passive"))
    )
    (net (code "65") (name "Net-(U2C-VCAP_1)") (class "Default")
      (node (ref "C9") (pin "1") (pinfunction "1_1") (pintype "passive"))
      (node (ref "U2") (pin "49") (pinfunction "VCAP_1_49") (pintype "power_in"))
    )
    (net (code "66") (name "Net-(U2C-VCAP_2)") (class "Default")
      (node (ref "C10") (pin "1") (pinfunction "1_1") (pintype "passive"))
      (node (ref "U2") (pin "73") (pinfunction "VCAP_2_73") (pintype "power_in"))
    )
    (net (code "67") (name "OCP") (class "Default")
      (node (ref "J6") (pin "01") (pinfunction "01_01") (pintype "passive"))
    )
    (net (code "68") (name "OVP") (class "Default")
      (node (ref "J6") (pin "02") (pinfunction "02_02") (pintype "passive"))
    )
    (net (code "69") (name "RESET") (class "Default")
      (node (ref "C12") (pin "1") (pinfunction "1_1") (pintype "passive"))
      (node (ref "J1") (pin "10") (pinfunction "10_10") (pintype "passive"))
      (node (ref "R3") (pin "1") (pinfunction "1_1") (pintype "passive"))
      (node (ref "SW1") (pin "1") (pinfunction "1_1") (pintype "passive"))
      (node (ref "U2") (pin "14") (pinfunction "NRST_14") (pintype "bidirectional"))
    )
    (net (code "70") (name "SPI_MISO") (class "Default")
      (node (ref "J4") (pin "05") (pinfunction "05_05") (pintype "passive"))
    )
    (net (code "71") (name "SPI_MOSI") (class "Default")
      (node (ref "J4") (pin "06") (pinfunction "06_06") (pintype "passive"))
    )
    (net (code "72") (name "SWDCLK") (class "Default")
      (node (ref "J1") (pin "4") (pinfunction "4_4") (pintype "passive"))
      (node (ref "U2") (pin "76") (pinfunction "PA14_76") (pintype "bidirectional"))
    )
    (net (code "73") (name "SWDIO") (class "Default")
      (node (ref "J1") (pin "2") (pinfunction "2_2") (pintype "passive"))
      (node (ref "U2") (pin "72") (pinfunction "PA13_72") (pintype "bidirectional"))
    )
    (net (code "74") (name "SWO") (class "Default")
      (node (ref "J1") (pin "6") (pinfunction "6_6") (pintype "passive"))
      (node (ref "U2") (pin "89") (pinfunction "PB3_89") (pintype "bidirectional"))
    )
    (net (code "75") (name "USART1_RX") (class "Default")
      (node (ref "J5") (pin "01") (pinfunction "01_01") (pintype "passive"))
    )
    (net (code "76") (name "USART1_TX") (class "Default")
      (node (ref "J5") (pin "02") (pinfunction "02_02") (pintype "passive"))
    )
    (net (code "77") (name "USART2_RX") (class "Default")
      (node (ref "J4") (pin "09") (pinfunction "09_09") (pintype "passive"))
    )
    (net (code "78") (name "USART2_TX") (class "Default")
      (node (ref "J4") (pin "10") (pinfunction "10_10") (pintype "passive"))
    )
    (net (code "79") (name "unconnected-(J1-Pad7)") (class "Default")
      (node (ref "J1") (pin "7") (pinfunction "7_7") (pintype "passive"))
    )
    (net (code "80") (name "unconnected-(J1-Pad8)") (class "Default")
      (node (ref "J1") (pin "8") (pinfunction "8_8") (pintype "passive"))
    )
    (net (code "81") (name "unconnected-(J3-DAT1-Pad8)") (class "Default")
      (node (ref "J3") (pin "8") (pinfunction "DAT1_8") (pintype "bidirectional+no_connect"))
    )
    (net (code "82") (name "unconnected-(J3-DAT2-Pad1)") (class "Default")
      (node (ref "J3") (pin "1") (pinfunction "DAT2_1") (pintype "bidirectional+no_connect"))
    )
    (net (code "83") (name "unconnected-(J3-PadCD)") (class "Default")
      (node (ref "J3") (pin "CD") (pinfunction "CD_CD") (pintype "passive+no_connect"))
    )
    (net (code "84") (name "unconnected-(J7-Pad01)") (class "Default")
      (node (ref "J7") (pin "01") (pinfunction "01_01") (pintype "passive"))
    )
    (net (code "85") (name "unconnected-(J7-Pad02)") (class "Default")
      (node (ref "J7") (pin "02") (pinfunction "02_02") (pintype "passive"))
    )
    (net (code "86") (name "unconnected-(J7-Pad04)") (class "Default")
      (node (ref "J7") (pin "04") (pinfunction "04_04") (pintype "passive"))
    )
    (net (code "87") (name "unconnected-(J7-Pad06)") (class "Default")
      (node (ref "J7") (pin "06") (pinfunction "06_06") (pintype "passive"))
    )
    (net (code "88") (name "unconnected-(J7-Pad07)") (class "Default")
      (node (ref "J7") (pin "07") (pinfunction "07_07") (pintype "passive"))
    )
    (net (code "89") (name "unconnected-(J7-Pad08)") (class "Default")
      (node (ref "J7") (pin "08") (pinfunction "08_08") (pintype "passive"))
    )
    (net (code "90") (name "unconnected-(J7-Pad09)") (class "Default")
      (node (ref "J7") (pin "09") (pinfunction "09_09") (pintype "passive"))
    )
    (net (code "91") (name "unconnected-(J7-Pad10)") (class "Default")
      (node (ref "J7") (pin "10") (pinfunction "10_10") (pintype "passive"))
    )
    (net (code "92") (name "unconnected-(SW1-Pad2)") (class "Default")
      (node (ref "SW1") (pin "2") (pinfunction "2_2") (pintype "passive+no_connect"))
    )
    (net (code "93") (name "unconnected-(SW1-Pad3)") (class "Default")
      (node (ref "SW1") (pin "3") (pinfunction "3_3") (pintype "passive+no_connect"))
    )
    (net (code "94") (name "unconnected-(U1-L{slash}M-Pad9)") (class "Default")
      (node (ref "U1") (pin "9") (pinfunction "L/M_9") (pintype "passive"))
    )
    (net (code "95") (name "unconnected-(U2A-PA0{slash}WKUP-Pad23)") (class "Default")
      (node (ref "U2") (pin "23") (pinfunction "PA0/WKUP_23") (pintype "bidirectional"))
    )
    (net (code "96") (name "unconnected-(U2A-PA1-Pad24)") (class "Default")
      (node (ref "U2") (pin "24") (pinfunction "PA1_24") (pintype "bidirectional"))
    )
    (net (code "97") (name "unconnected-(U2A-PA8-Pad67)") (class "Default")
      (node (ref "U2") (pin "67") (pinfunction "PA8_67") (pintype "bidirectional"))
    )
    (net (code "98") (name "unconnected-(U2A-PA9-Pad68)") (class "Default")
      (node (ref "U2") (pin "68") (pinfunction "PA9_68") (pintype "bidirectional"))
    )
    (net (code "99") (name "unconnected-(U2A-PA10-Pad69)") (class "Default")
      (node (ref "U2") (pin "69") (pinfunction "PA10_69") (pintype "bidirectional"))
    )
    (net (code "100") (name "unconnected-(U2A-PA11-Pad70)") (class "Default")
      (node (ref "U2") (pin "70") (pinfunction "PA11_70") (pintype "bidirectional"))
    )
    (net (code "101") (name "unconnected-(U2A-PA12-Pad71)") (class "Default")
      (node (ref "U2") (pin "71") (pinfunction "PA12_71") (pintype "bidirectional"))
    )
    (net (code "102") (name "unconnected-(U2A-PA15-Pad77)") (class "Default")
      (node (ref "U2") (pin "77") (pinfunction "PA15_77") (pintype "bidirectional"))
    )
    (net (code "103") (name "unconnected-(U2A-PB0-Pad35)") (class "Default")
      (node (ref "U2") (pin "35") (pinfunction "PB0_35") (pintype "bidirectional"))
    )
    (net (code "104") (name "unconnected-(U2A-PB1-Pad36)") (class "Default")
      (node (ref "U2") (pin "36") (pinfunction "PB1_36") (pintype "bidirectional"))
    )
    (net (code "105") (name "unconnected-(U2A-PB2{slash}BOOT1-Pad37)") (class "Default")
      (node (ref "U2") (pin "37") (pinfunction "PB2/BOOT1_37") (pintype "bidirectional"))
    )
    (net (code "106") (name "unconnected-(U2A-PB4-Pad90)") (class "Default")
      (node (ref "U2") (pin "90") (pinfunction "PB4_90") (pintype "bidirectional"))
    )
    (net (code "107") (name "unconnected-(U2A-PB5-Pad91)") (class "Default")
      (node (ref "U2") (pin "91") (pinfunction "PB5_91") (pintype "bidirectional"))
    )
    (net (code "108") (name "unconnected-(U2A-PB6-Pad92)") (class "Default")
      (node (ref "U2") (pin "92") (pinfunction "PB6_92") (pintype "bidirectional"))
    )
    (net (code "109") (name "unconnected-(U2A-PB7-Pad93)") (class "Default")
      (node (ref "U2") (pin "93") (pinfunction "PB7_93") (pintype "bidirectional"))
    )
    (net (code "110") (name "unconnected-(U2A-PB8-Pad95)") (class "Default")
      (node (ref "U2") (pin "95") (pinfunction "PB8_95") (pintype "bidirectional"))
    )
    (net (code "111") (name "unconnected-(U2A-PB9-Pad96)") (class "Default")
      (node (ref "U2") (pin "96") (pinfunction "PB9_96") (pintype "bidirectional"))
    )
    (net (code "112") (name "unconnected-(U2A-PB10-Pad47)") (class "Default")
      (node (ref "U2") (pin "47") (pinfunction "PB10_47") (pintype "bidirectional"))
    )
    (net (code "113") (name "unconnected-(U2A-PB11-Pad48)") (class "Default")
      (node (ref "U2") (pin "48") (pinfunction "PB11_48") (pintype "bidirectional"))
    )
    (net (code "114") (name "unconnected-(U2A-PC0-Pad15)") (class "Default")
      (node (ref "U2") (pin "15") (pinfunction "PC0_15") (pintype "bidirectional"))
    )
    (net (code "115") (name "unconnected-(U2A-PC6-Pad63)") (class "Default")
      (node (ref "U2") (pin "63") (pinfunction "PC6_63") (pintype "bidirectional"))
    )
    (net (code "116") (name "unconnected-(U2A-PC7-Pad64)") (class "Default")
      (node (ref "U2") (pin "64") (pinfunction "PC7_64") (pintype "bidirectional"))
    )
    (net (code "117") (name "unconnected-(U2A-PC8-Pad65)") (class "Default")
      (node (ref "U2") (pin "65") (pinfunction "PC8_65") (pintype "bidirectional"))
    )
    (net (code "118") (name "unconnected-(U2A-PC9-Pad66)") (class "Default")
      (node (ref "U2") (pin "66") (pinfunction "PC9_66") (pintype "bidirectional"))
    )
    (net (code "119") (name "unconnected-(U2A-PC10-Pad78)") (class "Default")
      (node (ref "U2") (pin "78") (pinfunction "PC10_78") (pintype "bidirectional"))
    )
    (net (code "120") (name "unconnected-(U2A-PC11-Pad79)") (class "Default")
      (node (ref "U2") (pin "79") (pinfunction "PC11_79") (pintype "bidirectional"))
    )
    (net (code "121") (name "unconnected-(U2A-PC13-Pad7)") (class "Default")
      (node (ref "U2") (pin "7") (pinfunction "PC13_7") (pintype "bidirectional"))
    )
    (net (code "122") (name "unconnected-(U2A-PC14{slash}OSC32_IN-Pad8)") (class "Default")
      (node (ref "U2") (pin "8") (pinfunction "PC14/OSC32_IN_8") (pintype "bidirectional"))
    )
    (net (code "123") (name "unconnected-(U2A-PC15{slash}OSC32_OUT-Pad9)") (class "Default")
      (node (ref "U2") (pin "9") (pinfunction "PC15/OSC32_OUT_9") (pintype "bidirectional"))
    )
    (net (code "124") (name "unconnected-(U2A-PD3-Pad84)") (class "Default")
      (node (ref "U2") (pin "84") (pinfunction "PD3_84") (pintype "bidirectional"))
    )
    (net (code "125") (name "unconnected-(U2A-PD4-Pad85)") (class "Default")
      (node (ref "U2") (pin "85") (pinfunction "PD4_85") (pintype "bidirectional"))
    )
    (net (code "126") (name "unconnected-(U2A-PD5-Pad86)") (class "Default")
      (node (ref "U2") (pin "86") (pinfunction "PD5_86") (pintype "bidirectional"))
    )
    (net (code "127") (name "unconnected-(U2A-PD6-Pad87)") (class "Default")
      (node (ref "U2") (pin "87") (pinfunction "PD6_87") (pintype "bidirectional"))
    )
    (net (code "128") (name "unconnected-(U2A-PD7-Pad88)") (class "Default")
      (node (ref "U2") (pin "88") (pinfunction "PD7_88") (pintype "bidirectional"))
    )
    (net (code "129") (name "unconnected-(U2A-PD8-Pad55)") (class "Default")
      (node (ref "U2") (pin "55") (pinfunction "PD8_55") (pintype "bidirectional"))
    )
    (net (code "130") (name "unconnected-(U2A-PD9-Pad56)") (class "Default")
      (node (ref "U2") (pin "56") (pinfunction "PD9_56") (pintype "bidirectional"))
    )
    (net (code "131") (name "unconnected-(U2A-PD10-Pad57)") (class "Default")
      (node (ref "U2") (pin "57") (pinfunction "PD10_57") (pintype "bidirectional"))
    )
    (net (code "132") (name "unconnected-(U2A-PD11-Pad58)") (class "Default")
      (node (ref "U2") (pin "58") (pinfunction "PD11_58") (pintype "bidirectional"))
    )
    (net (code "133") (name "unconnected-(U2A-PD12-Pad59)") (class "Default")
      (node (ref "U2") (pin "59") (pinfunction "PD12_59") (pintype "bidirectional"))
    )
    (net (code "134") (name "unconnected-(U2A-PD13-Pad60)") (class "Default")
      (node (ref "U2") (pin "60") (pinfunction "PD13_60") (pintype "bidirectional"))
    )
    (net (code "135") (name "unconnected-(U2A-PD14-Pad61)") (class "Default")
      (node (ref "U2") (pin "61") (pinfunction "PD14_61") (pintype "bidirectional"))
    )
    (net (code "136") (name "unconnected-(U2A-PD15-Pad62)") (class "Default")
      (node (ref "U2") (pin "62") (pinfunction "PD15_62") (pintype "bidirectional"))
    )
    (net (code "137") (name "unconnected-(U2A-PE0-Pad97)") (class "Default")
      (node (ref "U2") (pin "97") (pinfunction "PE0_97") (pintype "bidirectional"))
    )
    (net (code "138") (name "unconnected-(U2A-PE5-Pad4)") (class "Default")
      (node (ref "U2") (pin "4") (pinfunction "PE5_4") (pintype "bidirectional"))
    )
    (net (code "139") (name "unconnected-(U2A-PE6-Pad5)") (class "Default")
      (node (ref "U2") (pin "5") (pinfunction "PE6_5") (pintype "bidirectional"))
    )
    (net (code "140") (name "unconnected-(U2A-PE7-Pad38)") (class "Default")
      (node (ref "U2") (pin "38") (pinfunction "PE7_38") (pintype "bidirectional"))
    )
    (net (code "141") (name "unconnected-(U2A-PE8-Pad39)") (class "Default")
      (node (ref "U2") (pin "39") (pinfunction "PE8_39") (pintype "bidirectional"))
    )
    (net (code "142") (name "unconnected-(U2A-PE9-Pad40)") (class "Default")
      (node (ref "U2") (pin "40") (pinfunction "PE9_40") (pintype "bidirectional"))
    )
    (net (code "143") (name "unconnected-(U2A-PE10-Pad41)") (class "Default")
      (node (ref "U2") (pin "41") (pinfunction "PE10_41") (pintype "bidirectional"))
    )
    (net (code "144") (name "unconnected-(U2A-PE11-Pad42)") (class "Default")
      (node (ref "U2") (pin "42") (pinfunction "PE11_42") (pintype "bidirectional"))
    )
    (net (code "145") (name "unconnected-(U2A-PE12-Pad43)") (class "Default")
      (node (ref "U2") (pin "43") (pinfunction "PE12_43") (pintype "bidirectional"))
    )
    (net (code "146") (name "unconnected-(U2A-PE13-Pad44)") (class "Default")
      (node (ref "U2") (pin "44") (pinfunction "PE13_44") (pintype "bidirectional"))
    )
    (net (code "147") (name "unconnected-(U2A-PE14-Pad45)") (class "Default")
      (node (ref "U2") (pin "45") (pinfunction "PE14_45") (pintype "bidirectional"))
    )
    (net (code "148") (name "unconnected-(U2A-PE15-Pad46)") (class "Default")
      (node (ref "U2") (pin "46") (pinfunction "PE15_46") (pintype "bidirectional"))
    )
    (net (code "149") (name "unconnected-(U3B-NC-Pad8)") (class "Default")
      (node (ref "U3") (pin "8") (pinfunction "NC_8") (pintype "passive"))
    )
    (net (code "150") (name "unconnected-(U3B-NC-Pad9)") (class "Default")
      (node (ref "U3") (pin "9") (pinfunction "NC_9") (pintype "passive"))
    )
    (net (code "151") (name "unconnected-(U3B-NC-Pad10)") (class "Default")
      (node (ref "U3") (pin "10") (pinfunction "NC_10") (pintype "passive"))
    )
    (net (code "152") (name "unconnected-(U3B-NC-Pad11)") (class "Default")
      (node (ref "U3") (pin "11") (pinfunction "NC_11") (pintype "passive"))
    )
    (net (code "153") (name "unconnected-(U3B-NC-Pad12)") (class "Default")
      (node (ref "U3") (pin "12") (pinfunction "NC_12") (pintype "passive"))
    )
    (net (code "154") (name "unconnected-(U3B-NC-Pad13)") (class "Default")
      (node (ref "U3") (pin "13") (pinfunction "NC_13") (pintype "passive"))
    )
    (net (code "155") (name "unconnected-(U3B-NC-Pad14)") (class "Default")
      (node (ref "U3") (pin "14") (pinfunction "NC_14") (pintype "passive"))
    )
    (net (code "156") (name "unconnected-(U3B-NC-Pad15)") (class "Default")
      (node (ref "U3") (pin "15") (pinfunction "NC_15") (pintype "passive"))
    )
    (net (code "157") (name "unconnected-(U3B-NC-Pad16)") (class "Default")
      (node (ref "U3") (pin "16") (pinfunction "NC_16") (pintype "passive"))
    )
    (net (code "158") (name "unconnected-(U3B-NC-Pad17)") (class "Default")
      (node (ref "U3") (pin "17") (pinfunction "NC_17") (pintype "passive"))
    )
    (net (code "159") (name "unconnected-(U3B-NC-Pad18)") (class "Default")
      (node (ref "U3") (pin "18") (pinfunction "NC_18") (pintype "passive"))
    )
    (net (code "160") (name "unconnected-(U3B-NC-Pad19)") (class "Default")
      (node (ref "U3") (pin "19") (pinfunction "NC_19") (pintype "passive"))
    )
    (net (code "161") (name "unconnected-(U3B-NC-Pad25)") (class "Default")
      (node (ref "U3") (pin "25") (pinfunction "NC_25") (pintype "passive"))
    )
    (net (code "162") (name "unconnected-(U3B-NC-Pad27)") (class "Default")
      (node (ref "U3") (pin "27") (pinfunction "NC_27") (pintype "passive"))
    )
    (net (code "163") (name "unconnected-(U3B-NC-Pad28)") (class "Default")
      (node (ref "U3") (pin "28") (pinfunction "NC_28") (pintype "passive"))
    )
    (net (code "164") (name "unconnected-(U3B-NC-Pad29)") (class "Default")
      (node (ref "U3") (pin "29") (pinfunction "NC_29") (pintype "passive"))
    )
    (net (code "165") (name "unconnected-(U3B-NC-Pad30)") (class "Default")
      (node (ref "U3") (pin "30") (pinfunction "NC_30") (pintype "passive"))
    )
    (net (code "166") (name "unconnected-(U3B-NC-Pad32)") (class "Default")
      (node (ref "U3") (pin "32") (pinfunction "NC_32") (pintype "passive"))
    )
    (net (code "167") (name "unconnected-(U3B-RESERVED-Pad2)") (class "Default")
      (node (ref "U3") (pin "2") (pinfunction "RESERVED_2") (pintype "passive"))
    )
    (net (code "168") (name "unconnected-(U3B-RESERVED-Pad7)") (class "Default")
      (node (ref "U3") (pin "7") (pinfunction "RESERVED_7") (pintype "passive"))
    )
    (net (code "169") (name "unconnected-(U3B-RESERVED-Pad22)") (class "Default")
      (node (ref "U3") (pin "22") (pinfunction "RESERVED_22") (pintype "passive"))
    )
    (net (code "170") (name "unconnected-(U4-RESV-Pad2)") (class "Default")
      (node (ref "U4") (pin "2") (pinfunction "RESV_2") (pintype "passive"))
    )
    (net (code "171") (name "unconnected-(U4-RESV-Pad3)") (class "Default")
      (node (ref "U4") (pin "3") (pinfunction "RESV_3") (pintype "passive"))
    )
    (net (code "172") (name "unconnected-(U4-RESV-Pad10)") (class "Default")
      (node (ref "U4") (pin "10") (pinfunction "RESV_10") (pintype "passive"))
    )
    (net (code "173") (name "unconnected-(U4-RESV-Pad11)") (class "Default")
      (node (ref "U4") (pin "11") (pinfunction "RESV_11") (pintype "passive"))
    )
    (net (code "174") (name "unconnected-(U5-NC-Pad5)") (class "Default")
      (node (ref "U5") (pin "5") (pinfunction "NC_5") (pintype "passive"))
    )
    (net (code "175") (name "unconnected-(U6-EXTINT-Pad5)") (class "Default")
      (node (ref "U6") (pin "5") (pinfunction "EXTINT_5") (pintype "input+no_connect"))
    )
    (net (code "176") (name "unconnected-(U6-RESET_N-Pad9)") (class "Default")
      (node (ref "U6") (pin "9") (pinfunction "RESET_N_9") (pintype "input+no_connect"))
    )
    (net (code "177") (name "unconnected-(U6-SAFEBOOT_N-Pad18)") (class "Default")
      (node (ref "U6") (pin "18") (pinfunction "SAFEBOOT_N_18") (pintype "input+no_connect"))
    )
    (net (code "178") (name "unconnected-(U6-TIMEPULSE-Pad4)") (class "Default")
      (node (ref "U6") (pin "4") (pinfunction "TIMEPULSE_4") (pintype "output+no_connect"))
    )
    (net (code "179") (name "unconnected-(U6-VIO_SEL-Pad15)") (class "Default")
      (node (ref "U6") (pin "15") (pinfunction "VIO_SEL_15") (pintype "input+no_connect"))
    )
    (net (code "180") (name "unconnected-(U6-V_BCKP-Pad6)") (class "Default")
      (node (ref "U6") (pin "6") (pinfunction "V_BCKP_6") (pintype "power_in+no_connect"))
    )
    (net (code "181") (name "unconnected-(U8-EPAD-Pad7)") (class "Default")
      (node (ref "U8") (pin "7") (pinfunction "EPAD_7") (pintype "passive+no_connect"))
    )
  )
)
